# Tray2_ARM.net
KiCad netlist of a schematic drawn in Altium Designer
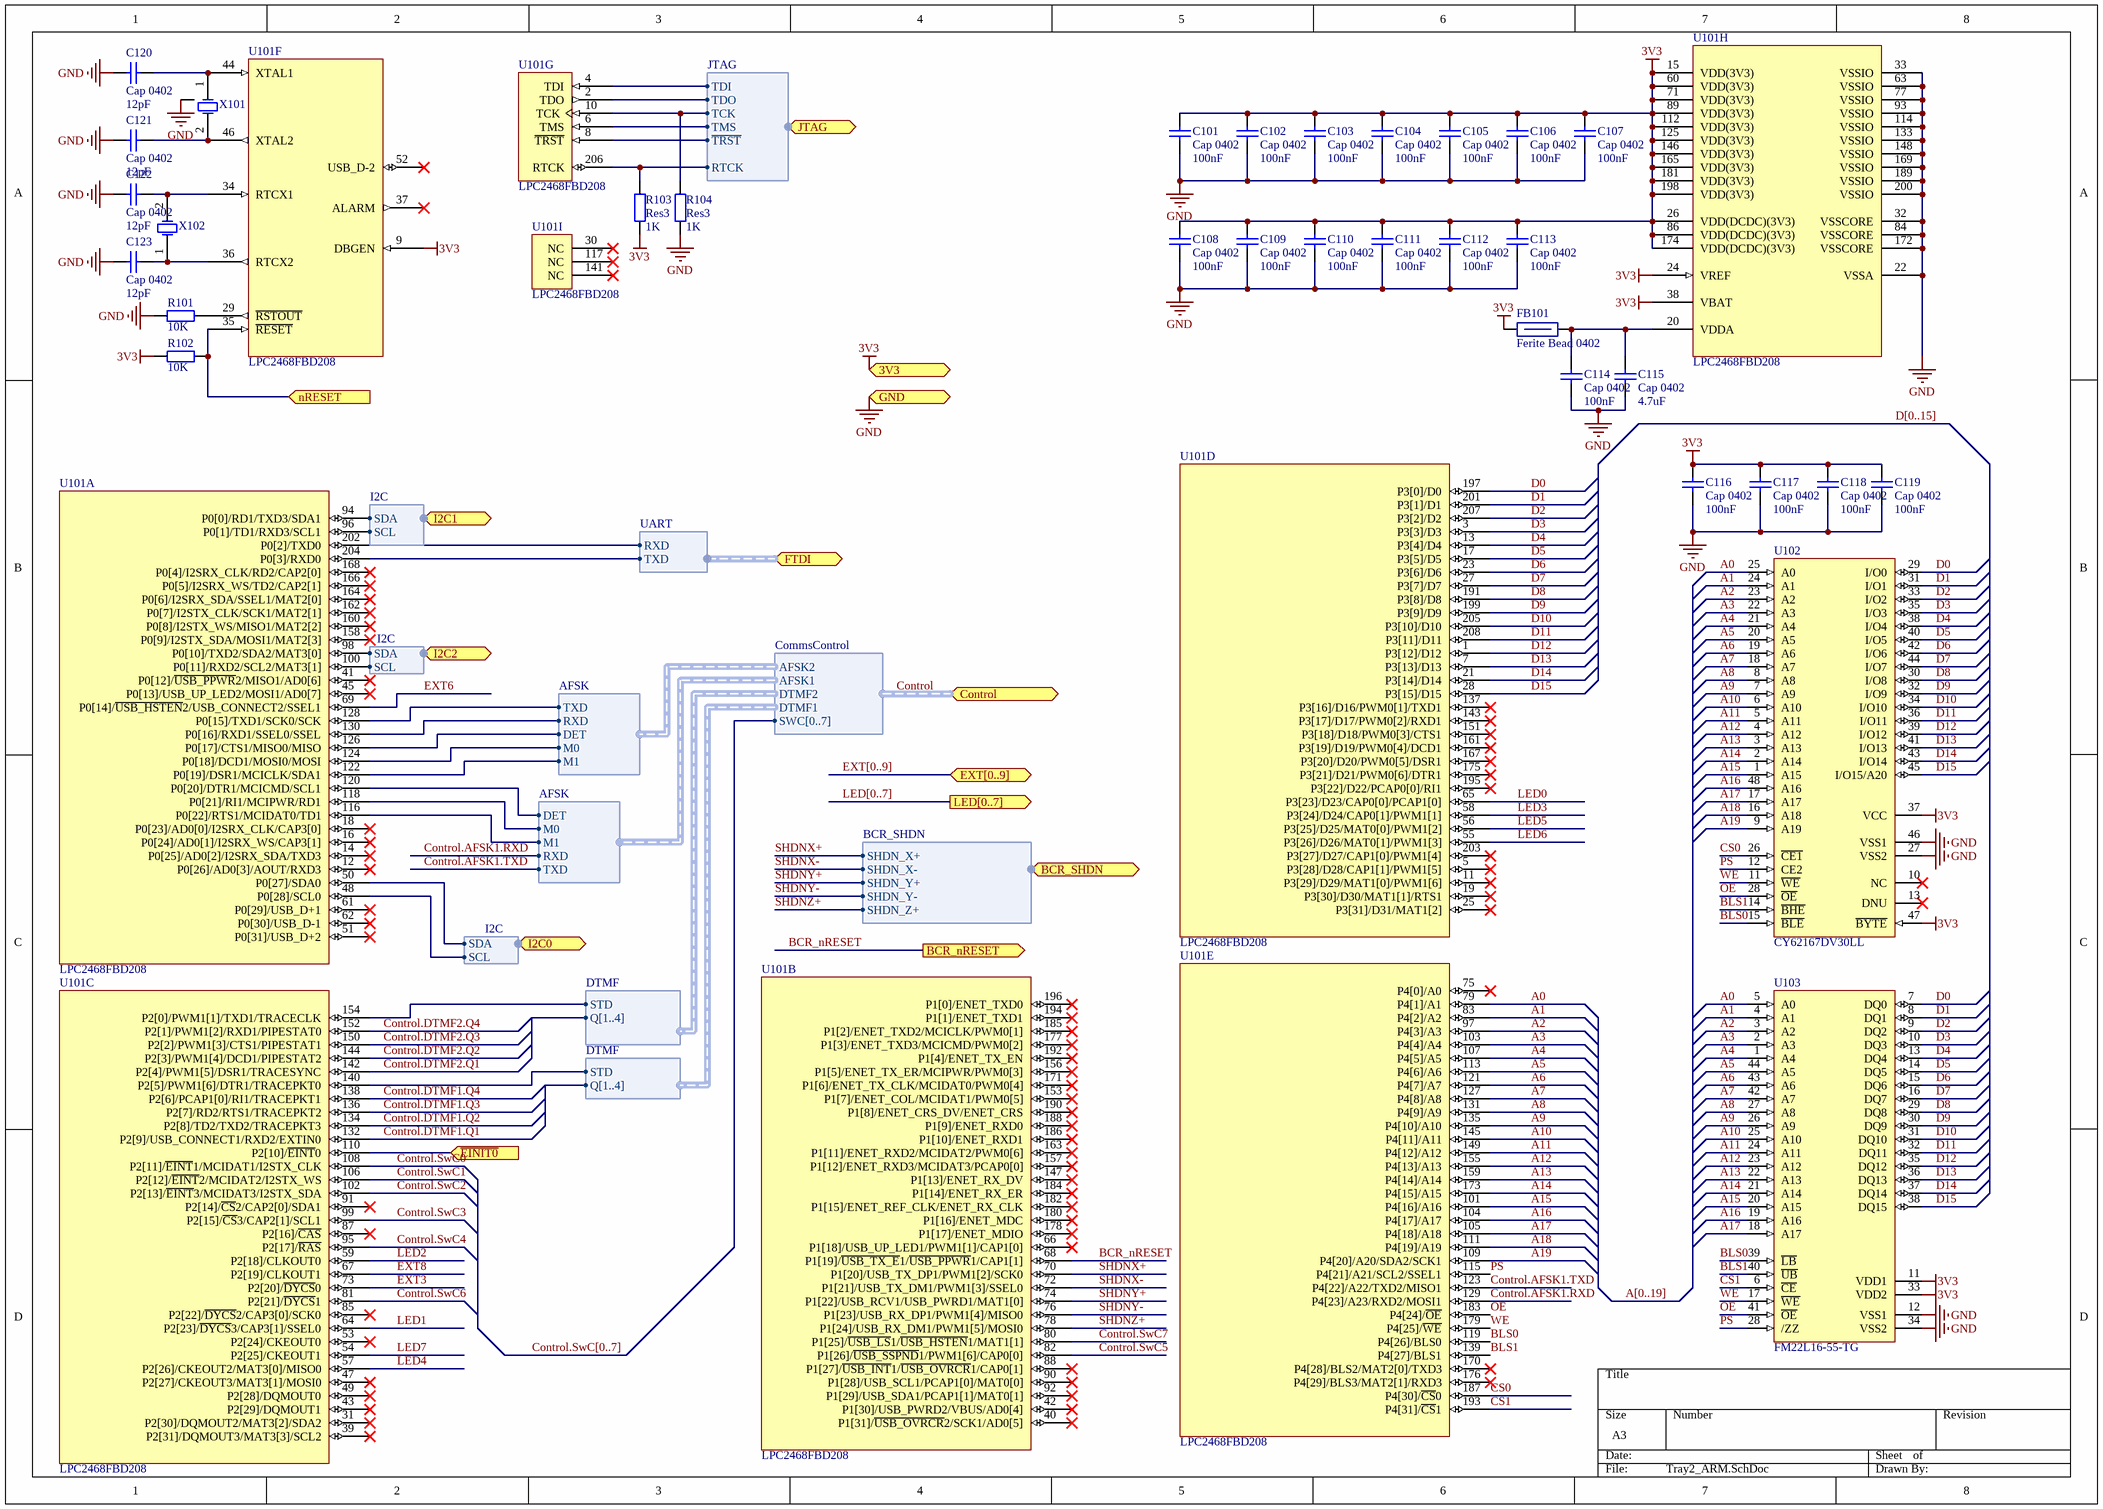
[diagram p0: Tray2_ARM.SchDoc]

(export (version "E")
  (design (tool "Eeschema 10.0.6"))
  (components
    (comp (ref "C101")
      (value "Cap 0402")
      (footprint "CAPC1005X06L")
      (description "Capacitor")
      (fields (field (name "ALTIUM_VALUE") "100nF") (field (name "PUBLISHER") "Altium Limited"))
      (libsource (lib "CSC") (part "Cap 0402"))
    )
    (comp (ref "C102")
      (value "Cap 0402")
      (footprint "CAPC1005X06L")
      (description "Capacitor")
      (fields (field (name "ALTIUM_VALUE") "100nF") (field (name "PUBLISHER") "Altium Limited"))
      (libsource (lib "CSC") (part "Cap 0402"))
    )
    (comp (ref "C103")
      (value "Cap 0402")
      (footprint "CAPC1005X06L")
      (description "Capacitor")
      (fields (field (name "ALTIUM_VALUE") "100nF") (field (name "PUBLISHER") "Altium Limited"))
      (libsource (lib "CSC") (part "Cap 0402"))
    )
    (comp (ref "C104")
      (value "Cap 0402")
      (footprint "CAPC1005X06L")
      (description "Capacitor")
      (fields (field (name "ALTIUM_VALUE") "100nF") (field (name "PUBLISHER") "Altium Limited"))
      (libsource (lib "CSC") (part "Cap 0402"))
    )
    (comp (ref "C105")
      (value "Cap 0402")
      (footprint "CAPC1005X06L")
      (description "Capacitor")
      (fields (field (name "ALTIUM_VALUE") "100nF") (field (name "PUBLISHER") "Altium Limited"))
      (libsource (lib "CSC") (part "Cap 0402"))
    )
    (comp (ref "C106")
      (value "Cap 0402")
      (footprint "CAPC1005X06L")
      (description "Capacitor")
      (fields (field (name "ALTIUM_VALUE") "100nF") (field (name "PUBLISHER") "Altium Limited"))
      (libsource (lib "CSC") (part "Cap 0402"))
    )
    (comp (ref "C107")
      (value "Cap 0402")
      (footprint "CAPC1005X06L")
      (description "Capacitor")
      (fields (field (name "ALTIUM_VALUE") "100nF") (field (name "PUBLISHER") "Altium Limited"))
      (libsource (lib "CSC") (part "Cap 0402"))
    )
    (comp (ref "C108")
      (value "Cap 0402")
      (footprint "CAPC1005X06L")
      (description "Capacitor")
      (fields (field (name "ALTIUM_VALUE") "100nF") (field (name "PUBLISHER") "Altium Limited"))
      (libsource (lib "CSC") (part "Cap 0402"))
    )
    (comp (ref "C109")
      (value "Cap 0402")
      (footprint "CAPC1005X06L")
      (description "Capacitor")
      (fields (field (name "ALTIUM_VALUE") "100nF") (field (name "PUBLISHER") "Altium Limited"))
      (libsource (lib "CSC") (part "Cap 0402"))
    )
    (comp (ref "C110")
      (value "Cap 0402")
      (footprint "CAPC1005X06L")
      (description "Capacitor")
      (fields (field (name "ALTIUM_VALUE") "100nF") (field (name "PUBLISHER") "Altium Limited"))
      (libsource (lib "CSC") (part "Cap 0402"))
    )
    (comp (ref "C111")
      (value "Cap 0402")
      (footprint "CAPC1005X06L")
      (description "Capacitor")
      (fields (field (name "ALTIUM_VALUE") "100nF") (field (name "PUBLISHER") "Altium Limited"))
      (libsource (lib "CSC") (part "Cap 0402"))
    )
    (comp (ref "C112")
      (value "Cap 0402")
      (footprint "CAPC1005X06L")
      (description "Capacitor")
      (fields (field (name "ALTIUM_VALUE") "100nF") (field (name "PUBLISHER") "Altium Limited"))
      (libsource (lib "CSC") (part "Cap 0402"))
    )
    (comp (ref "C113")
      (value "Cap 0402")
      (footprint "CAPC1005X06L")
      (description "Capacitor")
      (fields (field (name "ALTIUM_VALUE") "100nF") (field (name "PUBLISHER") "Altium Limited"))
      (libsource (lib "CSC") (part "Cap 0402"))
    )
    (comp (ref "C114")
      (value "Cap 0402")
      (footprint "CAPC1005X06L")
      (description "Capacitor")
      (fields (field (name "ALTIUM_VALUE") "100nF") (field (name "PUBLISHER") "Altium Limited"))
      (libsource (lib "CSC") (part "Cap 0402"))
    )
    (comp (ref "C115")
      (value "Cap 0402")
      (footprint "CAPC1005X06L")
      (description "Capacitor")
      (fields (field (name "ALTIUM_VALUE") "4.7uF") (field (name "PUBLISHER") "Altium Limited"))
      (libsource (lib "CSC") (part "Cap 0402"))
    )
    (comp (ref "C116")
      (value "Cap 0402")
      (footprint "CAPC1005X06L")
      (description "Capacitor")
      (fields (field (name "ALTIUM_VALUE") "100nF") (field (name "PUBLISHER") "Altium Limited"))
      (libsource (lib "CSC") (part "Cap 0402"))
    )
    (comp (ref "C117")
      (value "Cap 0402")
      (footprint "CAPC1005X06L")
      (description "Capacitor")
      (fields (field (name "ALTIUM_VALUE") "100nF") (field (name "PUBLISHER") "Altium Limited"))
      (libsource (lib "CSC") (part "Cap 0402"))
    )
    (comp (ref "C118")
      (value "Cap 0402")
      (footprint "CAPC1005X06L")
      (description "Capacitor")
      (fields (field (name "ALTIUM_VALUE") "100nF") (field (name "PUBLISHER") "Altium Limited"))
      (libsource (lib "CSC") (part "Cap 0402"))
    )
    (comp (ref "C119")
      (value "Cap 0402")
      (footprint "CAPC1005X06L")
      (description "Capacitor")
      (fields (field (name "ALTIUM_VALUE") "100nF") (field (name "PUBLISHER") "Altium Limited"))
      (libsource (lib "CSC") (part "Cap 0402"))
    )
    (comp (ref "C120")
      (value "Cap 0402")
      (footprint "CAPC1005X06L")
      (description "Capacitor")
      (fields (field (name "ALTIUM_VALUE") "12pF") (field (name "PUBLISHER") "Altium Limited"))
      (libsource (lib "CSC") (part "Cap 0402"))
    )
    (comp (ref "C121")
      (value "Cap 0402")
      (footprint "CAPC1005X06L")
      (description "Capacitor")
      (fields (field (name "ALTIUM_VALUE") "12pF") (field (name "PUBLISHER") "Altium Limited"))
      (libsource (lib "CSC") (part "Cap 0402"))
    )
    (comp (ref "C122")
      (value "Cap 0402")
      (footprint "CAPC1005X06L")
      (description "Capacitor")
      (fields (field (name "ALTIUM_VALUE") "12pF") (field (name "PUBLISHER") "Altium Limited"))
      (libsource (lib "CSC") (part "Cap 0402"))
    )
    (comp (ref "C123")
      (value "Cap 0402")
      (footprint "CAPC1005X06L")
      (description "Capacitor")
      (fields (field (name "ALTIUM_VALUE") "12pF") (field (name "PUBLISHER") "Altium Limited"))
      (libsource (lib "CSC") (part "Cap 0402"))
    )
    (comp (ref "FB101")
      (value "Ferite Bead 0402")
      (footprint "INDC1005X06L")
      (description "Ferite Bead : 0402")
      (fields (field (name "PUBLISHER") "Altium Limited"))
      (libsource (lib "CSC") (part "FB_0402"))
    )
    (comp (ref "R101")
      (value "10K")
      (footprint "RESC1005X06L")
      (description "Resistor")
      (fields (field (name "Comment") "Res3") (field (name "PUBLISHER") "Altium Limited"))
      (libsource (lib "") (part "Res3_1"))
    )
    (comp (ref "R102")
      (value "10K")
      (footprint "RESC1005X06L")
      (description "Resistor")
      (fields (field (name "Comment") "Res3") (field (name "PUBLISHER") "Altium Limited"))
      (libsource (lib "") (part "Res3_1"))
    )
    (comp (ref "R103")
      (value "Res3")
      (footprint "RESC1005X06L")
      (description "Resistor")
      (fields (field (name "ALTIUM_VALUE") "1K") (field (name "PUBLISHER") "Altium Limited"))
      (libsource (lib "CSC") (part "Res3"))
    )
    (comp (ref "R104")
      (value "Res3")
      (footprint "RESC1005X06L")
      (description "Resistor")
      (fields (field (name "ALTIUM_VALUE") "1K") (field (name "PUBLISHER") "Altium Limited"))
      (libsource (lib "CSC") (part "Res3"))
    )
    (comp (ref "U101")
      (value "LPC2468FBD208")
      (footprint "TSQFP50P3000X3000X160-208L")
      (description "ARM7 16/32-Bit Microcontroller, 512KB Flash, 98KB RAM, 208-Lead LQFP")
      (fields (field (name "PUBLISHER") "Altium Limited"))
      (libsource (lib "CSC") (part "LPC2468FBD208"))
    )
    (comp (ref "U102")
      (value "CY62167DV30LL")
      (footprint "TSSOP50P2000X120-48L")
      (description "16-Mbit (1M x 16) Static RAM")
      (fields (field (name "PUBLISHER") "Altium Limited"))
      (libsource (lib "CSC") (part "CY62167DV30LL"))
    )
    (comp (ref "U103")
      (value "FM22L16-55-TG")
      (footprint "TSOP80P1180X120-44L")
      (description "FRAM, 2MB, 3V, 60NS, 44TSOP2")
      (libsource (lib "CSC") (part "FM22L16-55-TG"))
    )
    (comp (ref "X101")
      (value "Crystal Oscilator")
      (footprint "7M")
      (description "Crystal Oscillator")
      (fields (field (name "PUBLISHER") "Altium Limited"))
      (libsource (lib "CSC") (part "C.O. 4pins"))
    )
    (comp (ref "X102")
      (value "Crystal Oscilator")
      (footprint "9H T10")
      (description "Crystal Oscillator")
      (fields (field (name "PUBLISHER") "Altium Limited"))
      (libsource (lib "CSC") (part "C.O. 2pins"))
    )
  )
  (nets
    (net (code "15") (name "/A0") (class "Default")
      (node (ref "U101") (pin "79") (pinfunction "P4[1]/A1_79") (pintype "bidirectional"))
      (node (ref "U102") (pin "25") (pinfunction "A0_25") (pintype "input"))
      (node (ref "U103") (pin "5") (pinfunction "A0_5") (pintype "input"))
    )
    (net (code "16") (name "/A1") (class "Default")
      (node (ref "U101") (pin "83") (pinfunction "P4[2]/A2_83") (pintype "bidirectional"))
      (node (ref "U102") (pin "24") (pinfunction "A1_24") (pintype "input"))
      (node (ref "U103") (pin "4") (pinfunction "A1_4") (pintype "input"))
    )
    (net (code "17") (name "/A2") (class "Default")
      (node (ref "U101") (pin "97") (pinfunction "P4[3]/A3_97") (pintype "bidirectional"))
      (node (ref "U102") (pin "23") (pinfunction "A2_23") (pintype "input"))
      (node (ref "U103") (pin "3") (pinfunction "A2_3") (pintype "input"))
    )
    (net (code "18") (name "/A3") (class "Default")
      (node (ref "U101") (pin "103") (pinfunction "P4[4]/A4_103") (pintype "bidirectional"))
      (node (ref "U102") (pin "22") (pinfunction "A3_22") (pintype "input"))
      (node (ref "U103") (pin "2") (pinfunction "A3_2") (pintype "input"))
    )
    (net (code "19") (name "/A4") (class "Default")
      (node (ref "U101") (pin "107") (pinfunction "P4[5]/A5_107") (pintype "bidirectional"))
      (node (ref "U102") (pin "21") (pinfunction "A4_21") (pintype "input"))
      (node (ref "U103") (pin "1") (pinfunction "A4_1") (pintype "input"))
    )
    (net (code "20") (name "/A5") (class "Default")
      (node (ref "U101") (pin "113") (pinfunction "P4[6]/A6_113") (pintype "bidirectional"))
      (node (ref "U102") (pin "20") (pinfunction "A5_20") (pintype "input"))
      (node (ref "U103") (pin "44") (pinfunction "A5_44") (pintype "input"))
    )
    (net (code "21") (name "/A6") (class "Default")
      (node (ref "U101") (pin "121") (pinfunction "P4[7]/A7_121") (pintype "bidirectional"))
      (node (ref "U102") (pin "19") (pinfunction "A6_19") (pintype "input"))
      (node (ref "U103") (pin "43") (pinfunction "A6_43") (pintype "input"))
    )
    (net (code "22") (name "/A7") (class "Default")
      (node (ref "U101") (pin "127") (pinfunction "P4[8]/A8_127") (pintype "bidirectional"))
      (node (ref "U102") (pin "18") (pinfunction "A7_18") (pintype "input"))
      (node (ref "U103") (pin "42") (pinfunction "A7_42") (pintype "input"))
    )
    (net (code "23") (name "/A8") (class "Default")
      (node (ref "U101") (pin "131") (pinfunction "P4[9]/A9_131") (pintype "bidirectional"))
      (node (ref "U102") (pin "8") (pinfunction "A8_8") (pintype "input"))
      (node (ref "U103") (pin "27") (pinfunction "A8_27") (pintype "input"))
    )
    (net (code "24") (name "/A9") (class "Default")
      (node (ref "U101") (pin "135") (pinfunction "P4[10]/A10_135") (pintype "bidirectional"))
      (node (ref "U102") (pin "7") (pinfunction "A9_7") (pintype "input"))
      (node (ref "U103") (pin "26") (pinfunction "A9_26") (pintype "input"))
    )
    (net (code "25") (name "/A10") (class "Default")
      (node (ref "U101") (pin "145") (pinfunction "P4[11]/A11_145") (pintype "bidirectional"))
      (node (ref "U102") (pin "6") (pinfunction "A10_6") (pintype "input"))
      (node (ref "U103") (pin "25") (pinfunction "A10_25") (pintype "input"))
    )
    (net (code "26") (name "/A11") (class "Default")
      (node (ref "U101") (pin "149") (pinfunction "P4[12]/A12_149") (pintype "bidirectional"))
      (node (ref "U102") (pin "5") (pinfunction "A11_5") (pintype "input"))
      (node (ref "U103") (pin "24") (pinfunction "A11_24") (pintype "input"))
    )
    (net (code "27") (name "/A12") (class "Default")
      (node (ref "U101") (pin "155") (pinfunction "P4[13]/A13_155") (pintype "bidirectional"))
      (node (ref "U102") (pin "4") (pinfunction "A12_4") (pintype "input"))
      (node (ref "U103") (pin "23") (pinfunction "A12_23") (pintype "input"))
    )
    (net (code "28") (name "/A13") (class "Default")
      (node (ref "U101") (pin "159") (pinfunction "P4[14]/A14_159") (pintype "bidirectional"))
      (node (ref "U102") (pin "3") (pinfunction "A13_3") (pintype "input"))
      (node (ref "U103") (pin "22") (pinfunction "A13_22") (pintype "input"))
    )
    (net (code "29") (name "/A14") (class "Default")
      (node (ref "U101") (pin "173") (pinfunction "P4[15]/A15_173") (pintype "bidirectional"))
      (node (ref "U102") (pin "2") (pinfunction "A14_2") (pintype "input"))
      (node (ref "U103") (pin "21") (pinfunction "A14_21") (pintype "input"))
    )
    (net (code "30") (name "/A15") (class "Default")
      (node (ref "U101") (pin "101") (pinfunction "P4[16]/A16_101") (pintype "bidirectional"))
      (node (ref "U102") (pin "1") (pinfunction "A15_1") (pintype "input"))
      (node (ref "U103") (pin "20") (pinfunction "A15_20") (pintype "input"))
    )
    (net (code "31") (name "/A16") (class "Default")
      (node (ref "U101") (pin "104") (pinfunction "P4[17]/A17_104") (pintype "bidirectional"))
      (node (ref "U102") (pin "48") (pinfunction "A16_48") (pintype "input"))
      (node (ref "U103") (pin "19") (pinfunction "A16_19") (pintype "input"))
    )
    (net (code "32") (name "/A17") (class "Default")
      (node (ref "U101") (pin "105") (pinfunction "P4[18]/A18_105") (pintype "bidirectional"))
      (node (ref "U102") (pin "17") (pinfunction "A17_17") (pintype "input"))
      (node (ref "U103") (pin "18") (pinfunction "A17_18") (pintype "input"))
    )
    (net (code "33") (name "/A18") (class "Default")
      (node (ref "U101") (pin "111") (pinfunction "P4[19]/A19_111") (pintype "bidirectional"))
      (node (ref "U102") (pin "16") (pinfunction "A18_16") (pintype "input"))
    )
    (net (code "34") (name "/A19") (class "Default")
      (node (ref "U101") (pin "109") (pinfunction "P4[20]/A20/SDA2/SCK1_109") (pintype "bidirectional"))
      (node (ref "U102") (pin "9") (pinfunction "A19_9") (pintype "input"))
    )
    (net (code "36") (name "/BCR_nRESET") (class "Default")
      (node (ref "U101") (pin "68") (pinfunction "P1[19]/~{USB_TX_E}1/~{USB_PPWR}1/CAP1[1]_68") (pintype "bidirectional"))
    )
    (net (code "37") (name "/BLS0") (class "Default")
      (node (ref "U101") (pin "119") (pinfunction "P4[26]/BLS0_119") (pintype "bidirectional"))
      (node (ref "U102") (pin "15") (pinfunction "~{BLE}_15") (pintype "input"))
      (node (ref "U103") (pin "39") (pinfunction "~{LB}_39") (pintype "input"))
    )
    (net (code "38") (name "/BLS1") (class "Default")
      (node (ref "U101") (pin "139") (pinfunction "P4[27]/BLS1_139") (pintype "bidirectional"))
      (node (ref "U102") (pin "14") (pinfunction "~{BHE}_14") (pintype "input"))
      (node (ref "U103") (pin "40") (pinfunction "~{UB}_40") (pintype "input"))
    )
    (net (code "39") (name "/CS0") (class "Default")
      (node (ref "U101") (pin "187") (pinfunction "P4[30]/~{CS}0_187") (pintype "bidirectional"))
      (node (ref "U102") (pin "26") (pinfunction "~{CE1}_26") (pintype "input"))
    )
    (net (code "40") (name "/CS1") (class "Default")
      (node (ref "U101") (pin "193") (pinfunction "P4[31]/~{CS}1_193") (pintype "bidirectional"))
      (node (ref "U103") (pin "6") (pinfunction "~{CE}_6") (pintype "input"))
    )
    (net (code "41") (name "/Control.AFSK1.RXD") (class "Default")
      (node (ref "U101") (pin "129") (pinfunction "P4[23]/A23/RXD2/MOSI1_129") (pintype "bidirectional"))
    )
    (net (code "42") (name "/Control.AFSK1.TXD") (class "Default")
      (node (ref "U101") (pin "123") (pinfunction "P4[22]/A22/TXD2/MISO1_123") (pintype "bidirectional"))
    )
    (net (code "43") (name "/Control.DTMF1.Q1") (class "Default")
      (node (ref "U101") (pin "132") (pinfunction "P2[9]/USB_CONNECT1/RXD2/EXTIN0_132") (pintype "bidirectional"))
    )
    (net (code "44") (name "/Control.DTMF1.Q2") (class "Default")
      (node (ref "U101") (pin "134") (pinfunction "P2[8]/TD2/TXD2/TRACEPKT3_134") (pintype "bidirectional"))
    )
    (net (code "45") (name "/Control.DTMF1.Q3") (class "Default")
      (node (ref "U101") (pin "136") (pinfunction "P2[7]/RD2/RTS1/TRACEPKT2_136") (pintype "bidirectional"))
    )
    (net (code "46") (name "/Control.DTMF1.Q4") (class "Default")
      (node (ref "U101") (pin "138") (pinfunction "P2[6]/PCAP1[0]/RI1/TRACEPKT1_138") (pintype "bidirectional"))
    )
    (net (code "47") (name "/Control.DTMF2.Q1") (class "Default")
      (node (ref "U101") (pin "142") (pinfunction "P2[4]/PWM1[5]/DSR1/TRACESYNC_142") (pintype "bidirectional"))
    )
    (net (code "48") (name "/Control.DTMF2.Q2") (class "Default")
      (node (ref "U101") (pin "144") (pinfunction "P2[3]/PWM1[4]/DCD1/PIPESTAT2_144") (pintype "bidirectional"))
    )
    (net (code "49") (name "/Control.DTMF2.Q3") (class "Default")
      (node (ref "U101") (pin "150") (pinfunction "P2[2]/PWM1[3]/CTS1/PIPESTAT1_150") (pintype "bidirectional"))
    )
    (net (code "50") (name "/Control.DTMF2.Q4") (class "Default")
      (node (ref "U101") (pin "152") (pinfunction "P2[1]/PWM1[2]/RXD1/PIPESTAT0_152") (pintype "bidirectional"))
    )
    (net (code "51") (name "/Control.SwC0") (class "Default")
      (node (ref "U101") (pin "108") (pinfunction "P2[11]/~{EINT}1/MCIDAT1/I2STX_CLK_108") (pintype "bidirectional"))
    )
    (net (code "52") (name "/Control.SwC1") (class "Default")
      (node (ref "U101") (pin "106") (pinfunction "P2[12]/~{EINT}2/MCIDAT2/I2STX_WS_106") (pintype "bidirectional"))
    )
    (net (code "53") (name "/Control.SwC2") (class "Default")
      (node (ref "U101") (pin "102") (pinfunction "P2[13]/~{EINT}3/MCIDAT3/I2STX_SDA_102") (pintype "bidirectional"))
    )
    (net (code "54") (name "/Control.SwC3") (class "Default")
      (node (ref "U101") (pin "99") (pinfunction "P2[15]/~{CS}3/CAP2[1]/SCL1_99") (pintype "bidirectional"))
    )
    (net (code "55") (name "/Control.SwC4") (class "Default")
      (node (ref "U101") (pin "95") (pinfunction "P2[17]/~{RAS}_95") (pintype "bidirectional"))
    )
    (net (code "56") (name "/Control.SwC5") (class "Default")
      (node (ref "U101") (pin "82") (pinfunction "P1[26]/~{USB_SSPND}1/PWM1[6]/CAP0[0]_82") (pintype "bidirectional"))
    )
    (net (code "57") (name "/Control.SwC6") (class "Default")
      (node (ref "U101") (pin "81") (pinfunction "P2[21]/~{DYCS}1_81") (pintype "bidirectional"))
    )
    (net (code "58") (name "/Control.SwC7") (class "Default")
      (node (ref "U101") (pin "80") (pinfunction "P1[25]/~{USB_LS}1/~{USB_HSTEN}1/MAT1[1]_80") (pintype "bidirectional"))
    )
    (net (code "59") (name "/D0") (class "Default")
      (node (ref "U101") (pin "197") (pinfunction "P3[0]/D0_197") (pintype "bidirectional"))
      (node (ref "U102") (pin "29") (pinfunction "I/O0_29") (pintype "bidirectional"))
      (node (ref "U103") (pin "7") (pinfunction "DQ0_7") (pintype "bidirectional"))
    )
    (net (code "60") (name "/D1") (class "Default")
      (node (ref "U101") (pin "201") (pinfunction "P3[1]/D1_201") (pintype "bidirectional"))
      (node (ref "U102") (pin "31") (pinfunction "I/O1_31") (pintype "bidirectional"))
      (node (ref "U103") (pin "8") (pinfunction "DQ1_8") (pintype "bidirectional"))
    )
    (net (code "61") (name "/D2") (class "Default")
      (node (ref "U101") (pin "207") (pinfunction "P3[2]/D2_207") (pintype "bidirectional"))
      (node (ref "U102") (pin "33") (pinfunction "I/O2_33") (pintype "bidirectional"))
      (node (ref "U103") (pin "9") (pinfunction "DQ2_9") (pintype "bidirectional"))
    )
    (net (code "62") (name "/D3") (class "Default")
      (node (ref "U101") (pin "3") (pinfunction "P3[3]/D3_3") (pintype "bidirectional"))
      (node (ref "U102") (pin "35") (pinfunction "I/O3_35") (pintype "bidirectional"))
      (node (ref "U103") (pin "10") (pinfunction "DQ3_10") (pintype "bidirectional"))
    )
    (net (code "63") (name "/D4") (class "Default")
      (node (ref "U101") (pin "13") (pinfunction "P3[4]/D4_13") (pintype "bidirectional"))
      (node (ref "U102") (pin "38") (pinfunction "I/O4_38") (pintype "bidirectional"))
      (node (ref "U103") (pin "13") (pinfunction "DQ4_13") (pintype "bidirectional"))
    )
    (net (code "64") (name "/D5") (class "Default")
      (node (ref "U101") (pin "17") (pinfunction "P3[5]/D5_17") (pintype "bidirectional"))
      (node (ref "U102") (pin "40") (pinfunction "I/O5_40") (pintype "bidirectional"))
      (node (ref "U103") (pin "14") (pinfunction "DQ5_14") (pintype "bidirectional"))
    )
    (net (code "65") (name "/D6") (class "Default")
      (node (ref "U101") (pin "23") (pinfunction "P3[6]/D6_23") (pintype "bidirectional"))
      (node (ref "U102") (pin "42") (pinfunction "I/O6_42") (pintype "bidirectional"))
      (node (ref "U103") (pin "15") (pinfunction "DQ6_15") (pintype "bidirectional"))
    )
    (net (code "66") (name "/D7") (class "Default")
      (node (ref "U101") (pin "27") (pinfunction "P3[7]/D7_27") (pintype "bidirectional"))
      (node (ref "U102") (pin "44") (pinfunction "I/O7_44") (pintype "bidirectional"))
      (node (ref "U103") (pin "16") (pinfunction "DQ7_16") (pintype "bidirectional"))
    )
    (net (code "67") (name "/D8") (class "Default")
      (node (ref "U101") (pin "191") (pinfunction "P3[8]/D8_191") (pintype "bidirectional"))
      (node (ref "U102") (pin "30") (pinfunction "I/O8_30") (pintype "bidirectional"))
      (node (ref "U103") (pin "29") (pinfunction "DQ8_29") (pintype "bidirectional"))
    )
    (net (code "68") (name "/D9") (class "Default")
      (node (ref "U101") (pin "199") (pinfunction "P3[9]/D9_199") (pintype "bidirectional"))
      (node (ref "U102") (pin "32") (pinfunction "I/O9_32") (pintype "bidirectional"))
      (node (ref "U103") (pin "30") (pinfunction "DQ9_30") (pintype "bidirectional"))
    )
    (net (code "69") (name "/D10") (class "Default")
      (node (ref "U101") (pin "205") (pinfunction "P3[10]/D10_205") (pintype "bidirectional"))
      (node (ref "U102") (pin "34") (pinfunction "I/O10_34") (pintype "bidirectional"))
      (node (ref "U103") (pin "31") (pinfunction "DQ10_31") (pintype "bidirectional"))
    )
    (net (code "70") (name "/D11") (class "Default")
      (node (ref "U101") (pin "208") (pinfunction "P3[11]/D11_208") (pintype "bidirectional"))
      (node (ref "U102") (pin "36") (pinfunction "I/O11_36") (pintype "bidirectional"))
      (node (ref "U103") (pin "32") (pinfunction "DQ11_32") (pintype "bidirectional"))
    )
    (net (code "71") (name "/D12") (class "Default")
      (node (ref "U101") (pin "1") (pinfunction "P3[12]/D12_1") (pintype "bidirectional"))
      (node (ref "U102") (pin "39") (pinfunction "I/O12_39") (pintype "bidirectional"))
      (node (ref "U103") (pin "35") (pinfunction "DQ12_35") (pintype "bidirectional"))
    )
    (net (code "72") (name "/D13") (class "Default")
      (node (ref "U101") (pin "7") (pinfunction "P3[13]/D13_7") (pintype "bidirectional"))
      (node (ref "U102") (pin "41") (pinfunction "I/O13_41") (pintype "bidirectional"))
      (node (ref "U103") (pin "36") (pinfunction "DQ13_36") (pintype "bidirectional"))
    )
    (net (code "73") (name "/D14") (class "Default")
      (node (ref "U101") (pin "21") (pinfunction "P3[14]/D14_21") (pintype "bidirectional"))
      (node (ref "U102") (pin "43") (pinfunction "I/O14_43") (pintype "bidirectional"))
      (node (ref "U103") (pin "37") (pinfunction "DQ14_37") (pintype "bidirectional"))
    )
    (net (code "74") (name "/D15") (class "Default")
      (node (ref "U101") (pin "28") (pinfunction "P3[15]/D15_28") (pintype "bidirectional"))
      (node (ref "U102") (pin "45") (pinfunction "I/O15/A20_45") (pintype "bidirectional"))
      (node (ref "U103") (pin "38") (pinfunction "DQ15_38") (pintype "bidirectional"))
    )
    (net (code "77") (name "/EXT3") (class "Default")
      (node (ref "U101") (pin "73") (pinfunction "P2[20]/~{DYCS}0_73") (pintype "bidirectional"))
    )
    (net (code "78") (name "/EXT6") (class "Default")
      (node (ref "U101") (pin "69") (pinfunction "P0[14]/~{USB_HSTEN}2/USB_CONNECT2/SSEL1_69") (pintype "bidirectional"))
    )
    (net (code "79") (name "/EXT8") (class "Default")
      (node (ref "U101") (pin "67") (pinfunction "P2[19]/CLKOUT1_67") (pintype "bidirectional"))
    )
    (net (code "81") (name "/LED0") (class "Default")
      (node (ref "U101") (pin "65") (pinfunction "P3[23]/D23/CAP0[0]/PCAP1[0]_65") (pintype "bidirectional"))
    )
    (net (code "82") (name "/LED1") (class "Default")
      (node (ref "U101") (pin "64") (pinfunction "P2[23]/~{DYCS}3/CAP3[1]/SSEL0_64") (pintype "bidirectional"))
    )
    (net (code "83") (name "/LED2") (class "Default")
      (node (ref "U101") (pin "59") (pinfunction "P2[18]/CLKOUT0_59") (pintype "bidirectional"))
    )
    (net (code "84") (name "/LED3") (class "Default")
      (node (ref "U101") (pin "58") (pinfunction "P3[24]/D24/CAP0[1]/PWM1[1]_58") (pintype "bidirectional"))
    )
    (net (code "85") (name "/LED4") (class "Default")
      (node (ref "U101") (pin "57") (pinfunction "P2[26]/CKEOUT2/MAT3[0]/MISO0_57") (pintype "bidirectional"))
    )
    (net (code "86") (name "/LED5") (class "Default")
      (node (ref "U101") (pin "56") (pinfunction "P3[25]/D25/MAT0[0]/PWM1[2]_56") (pintype "bidirectional"))
    )
    (net (code "87") (name "/LED6") (class "Default")
      (node (ref "U101") (pin "55") (pinfunction "P3[26]/D26/MAT0[1]/PWM1[3]_55") (pintype "bidirectional"))
    )
    (net (code "88") (name "/LED7") (class "Default")
      (node (ref "U101") (pin "54") (pinfunction "P2[25]/CKEOUT1_54") (pintype "bidirectional"))
    )
    (net (code "90") (name "/OE") (class "Default")
      (node (ref "U101") (pin "183") (pinfunction "P4[24]/~{OE}_183") (pintype "bidirectional"))
      (node (ref "U102") (pin "28") (pinfunction "~{OE}_28") (pintype "input"))
      (node (ref "U103") (pin "41") (pinfunction "~{OE}_41") (pintype "input"))
    )
    (net (code "91") (name "/PS") (class "Default")
      (node (ref "U101") (pin "115") (pinfunction "P4[21]/A21/SCL2/SSEL1_115") (pintype "bidirectional"))
      (node (ref "U102") (pin "12") (pinfunction "CE2_12") (pintype "input"))
      (node (ref "U103") (pin "28") (pinfunction "/ZZ_28") (pintype "input"))
    )
    (net (code "92") (name "/RTCK") (class "Default")
      (node (ref "R103") (pin "1") (pinfunction "1_1") (pintype "passive"))
      (node (ref "U101") (pin "206") (pinfunction "RTCK_206") (pintype "bidirectional"))
    )
    (net (code "93") (name "/SHDNX+") (class "Default")
      (node (ref "U101") (pin "70") (pinfunction "P1[20]/USB_TX_DP1/PWM1[2]/SCK0_70") (pintype "bidirectional"))
    )
    (net (code "94") (name "/SHDNX-") (class "Default")
      (node (ref "U101") (pin "72") (pinfunction "P1[21]/USB_TX_DM1/PWM1[3]/SSEL0_72") (pintype "bidirectional"))
    )
    (net (code "95") (name "/SHDNY+") (class "Default")
      (node (ref "U101") (pin "74") (pinfunction "P1[22]/USB_RCV1/USB_PWRD1/MAT1[0]_74") (pintype "bidirectional"))
    )
    (net (code "96") (name "/SHDNY-") (class "Default")
      (node (ref "U101") (pin "76") (pinfunction "P1[23]/USB_RX_DP1/PWM1[4]/MISO0_76") (pintype "bidirectional"))
    )
    (net (code "97") (name "/SHDNZ+") (class "Default")
      (node (ref "U101") (pin "78") (pinfunction "P1[24]/USB_RX_DM1/PWM1[5]/MOSI0_78") (pintype "bidirectional"))
    )
    (net (code "98") (name "/TCK") (class "Default")
      (node (ref "R104") (pin "1") (pinfunction "1_1") (pintype "passive"))
      (node (ref "U101") (pin "10") (pinfunction "TCK_10") (pintype "input"))
    )
    (net (code "99") (name "/TDI") (class "Default")
      (node (ref "U101") (pin "4") (pinfunction "TDI_4") (pintype "input"))
    )
    (net (code "100") (name "/TDO") (class "Default")
      (node (ref "U101") (pin "2") (pinfunction "TDO_2") (pintype "output"))
    )
    (net (code "101") (name "/TMS") (class "Default")
      (node (ref "U101") (pin "6") (pinfunction "TMS_6") (pintype "input"))
    )
    (net (code "102") (name "/WE") (class "Default")
      (node (ref "U101") (pin "179") (pinfunction "P4[25]/~{WE}_179") (pintype "bidirectional"))
      (node (ref "U102") (pin "11") (pinfunction "~{WE}_11") (pintype "input"))
      (node (ref "U103") (pin "17") (pinfunction "~{WE}_17") (pintype "input"))
    )
    (net (code "103") (name "/nRESET") (class "Default")
      (node (ref "R102") (pin "1") (pinfunction "1_1") (pintype "passive"))
      (node (ref "U101") (pin "35") (pinfunction "~{RESET}_35") (pintype "input"))
    )
    (net (code "111") (name "/~{EINIT0}") (class "Default")
      (node (ref "U101") (pin "110") (pinfunction "P2[10]/~{EINT}0_110") (pintype "bidirectional"))
    )
    (net (code "112") (name "/~{TRST}") (class "Default")
      (node (ref "U101") (pin "8") (pinfunction "~{TRST}_8") (pintype "input"))
    )
    (net (code "113") (name "3V3") (class "Default")
      (node (ref "C101") (pin "2") (pinfunction "2_2") (pintype "passive"))
      (node (ref "C102") (pin "2") (pinfunction "2_2") (pintype "passive"))
      (node (ref "C103") (pin "2") (pinfunction "2_2") (pintype "passive"))
      (node (ref "C104") (pin "2") (pinfunction "2_2") (pintype "passive"))
      (node (ref "C105") (pin "2") (pinfunction "2_2") (pintype "passive"))
      (node (ref "C106") (pin "2") (pinfunction "2_2") (pintype "passive"))
      (node (ref "C107") (pin "2") (pinfunction "2_2") (pintype "passive"))
      (node (ref "C108") (pin "2") (pinfunction "2_2") (pintype "passive"))
      (node (ref "C109") (pin "2") (pinfunction "2_2") (pintype "passive"))
      (node (ref "C110") (pin "2") (pinfunction "2_2") (pintype "passive"))
      (node (ref "C111") (pin "2") (pinfunction "2_2") (pintype "passive"))
      (node (ref "C112") (pin "2") (pinfunction "2_2") (pintype "passive"))
      (node (ref "C113") (pin "2") (pinfunction "2_2") (pintype "passive"))
      (node (ref "C116") (pin "2") (pinfunction "2_2") (pintype "passive"))
      (node (ref "C117") (pin "2") (pinfunction "2_2") (pintype "passive"))
      (node (ref "C118") (pin "2") (pinfunction "2_2") (pintype "passive"))
      (node (ref "C119") (pin "2") (pinfunction "2_2") (pintype "passive"))
      (node (ref "FB101") (pin "1") (pinfunction "1_1") (pintype "passive"))
      (node (ref "R102") (pin "2") (pinfunction "2_2") (pintype "passive"))
      (node (ref "R103") (pin "2") (pinfunction "2_2") (pintype "passive"))
      (node (ref "U101") (pin "112") (pinfunction "VDD(3V3)_112") (pintype "power_in"))
      (node (ref "U101") (pin "125") (pinfunction "VDD(3V3)_125") (pintype "power_in"))
      (node (ref "U101") (pin "146") (pinfunction "VDD(3V3)_146") (pintype "power_in"))
      (node (ref "U101") (pin "15") (pinfunction "VDD(3V3)_15") (pintype "power_in"))
      (node (ref "U101") (pin "165") (pinfunction "VDD(3V3)_165") (pintype "power_in"))
      (node (ref "U101") (pin "174") (pinfunction "VDD(DCDC)(3V3)_174") (pintype "power_in"))
      (node (ref "U101") (pin "181") (pinfunction "VDD(3V3)_181") (pintype "power_in"))
      (node (ref "U101") (pin "198") (pinfunction "VDD(3V3)_198") (pintype "power_in"))
      (node (ref "U101") (pin "24") (pinfunction "VREF_24") (pintype "input"))
      (node (ref "U101") (pin "26") (pinfunction "VDD(DCDC)(3V3)_26") (pintype "power_in"))
      (node (ref "U101") (pin "38") (pinfunction "VBAT_38") (pintype "power_in"))
      (node (ref "U101") (pin "60") (pinfunction "VDD(3V3)_60") (pintype "power_in"))
      (node (ref "U101") (pin "71") (pinfunction "VDD(3V3)_71") (pintype "power_in"))
      (node (ref "U101") (pin "86") (pinfunction "VDD(DCDC)(3V3)_86") (pintype "power_in"))
      (node (ref "U101") (pin "89") (pinfunction "VDD(3V3)_89") (pintype "power_in"))
      (node (ref "U101") (pin "9") (pinfunction "DBGEN_9") (pintype "input"))
      (node (ref "U102") (pin "37") (pinfunction "VCC_37") (pintype "power_in"))
      (node (ref "U102") (pin "47") (pinfunction "~{BYTE}_47") (pintype "input"))
      (node (ref "U103") (pin "11") (pinfunction "VDD1_11") (pintype "power_in"))
      (node (ref "U103") (pin "33") (pinfunction "VDD2_33") (pintype "power_in"))
    )
    (net (code "114") (name "GND") (class "Default")
      (node (ref "C101") (pin "1") (pinfunction "1_1") (pintype "passive"))
      (node (ref "C102") (pin "1") (pinfunction "1_1") (pintype "passive"))
      (node (ref "C103") (pin "1") (pinfunction "1_1") (pintype "passive"))
      (node (ref "C104") (pin "1") (pinfunction "1_1") (pintype "passive"))
      (node (ref "C105") (pin "1") (pinfunction "1_1") (pintype "passive"))
      (node (ref "C106") (pin "1") (pinfunction "1_1") (pintype "passive"))
      (node (ref "C107") (pin "1") (pinfunction "1_1") (pintype "passive"))
      (node (ref "C108") (pin "1") (pinfunction "1_1") (pintype "passive"))
      (node (ref "C109") (pin "1") (pinfunction "1_1") (pintype "passive"))
      (node (ref "C110") (pin "1") (pinfunction "1_1") (pintype "passive"))
      (node (ref "C111") (pin "1") (pinfunction "1_1") (pintype "passive"))
      (node (ref "C112") (pin "1") (pinfunction "1_1") (pintype "passive"))
      (node (ref "C113") (pin "1") (pinfunction "1_1") (pintype "passive"))
      (node (ref "C114") (pin "1") (pinfunction "1_1") (pintype "passive"))
      (node (ref "C115") (pin "1") (pinfunction "1_1") (pintype "passive"))
      (node (ref "C116") (pin "1") (pinfunction "1_1") (pintype "passive"))
      (node (ref "C117") (pin "1") (pinfunction "1_1") (pintype "passive"))
      (node (ref "C118") (pin "1") (pinfunction "1_1") (pintype "passive"))
      (node (ref "C119") (pin "1") (pinfunction "1_1") (pintype "passive"))
      (node (ref "C120") (pin "2") (pinfunction "2_2") (pintype "passive"))
      (node (ref "C121") (pin "1") (pinfunction "1_1") (pintype "passive"))
      (node (ref "C122") (pin "2") (pinfunction "2_2") (pintype "passive"))
      (node (ref "C123") (pin "1") (pinfunction "1_1") (pintype "passive"))
      (node (ref "R101") (pin "2") (pinfunction "2_2") (pintype "passive"))
      (node (ref "R104") (pin "2") (pinfunction "2_2") (pintype "passive"))
      (node (ref "U101") (pin "114") (pinfunction "VSSIO_114") (pintype "power_in"))
      (node (ref "U101") (pin "133") (pinfunction "VSSIO_133") (pintype "power_in"))
      (node (ref "U101") (pin "148") (pinfunction "VSSIO_148") (pintype "power_in"))
      (node (ref "U101") (pin "169") (pinfunction "VSSIO_169") (pintype "power_in"))
      (node (ref "U101") (pin "172") (pinfunction "VSSCORE_172") (pintype "power_in"))
      (node (ref "U101") (pin "189") (pinfunction "VSSIO_189") (pintype "power_in"))
      (node (ref "U101") (pin "200") (pinfunction "VSSIO_200") (pintype "power_in"))
      (node (ref "U101") (pin "22") (pinfunction "VSSA_22") (pintype "power_in"))
      (node (ref "U101") (pin "32") (pinfunction "VSSCORE_32") (pintype "power_in"))
      (node (ref "U101") (pin "33") (pinfunction "VSSIO_33") (pintype "power_in"))
      (node (ref "U101") (pin "63") (pinfunction "VSSIO_63") (pintype "power_in"))
      (node (ref "U101") (pin "77") (pinfunction "VSSIO_77") (pintype "power_in"))
      (node (ref "U101") (pin "84") (pinfunction "VSSCORE_84") (pintype "power_in"))
      (node (ref "U101") (pin "93") (pinfunction "VSSIO_93") (pintype "power_in"))
      (node (ref "U102") (pin "27") (pinfunction "VSS2_27") (pintype "power_in"))
      (node (ref "U102") (pin "46") (pinfunction "VSS1_46") (pintype "power_in"))
      (node (ref "U103") (pin "12") (pinfunction "VSS1_12") (pintype "power_in"))
      (node (ref "U103") (pin "34") (pinfunction "VSS2_34") (pintype "power_in"))
      (node (ref "X101") (pin "3") (pinfunction "3_3") (pintype "passive"))
    )
    (net (code "115") (name "Net-(U101F-RTCX1)") (class "Default")
      (node (ref "C122") (pin "1") (pinfunction "1_1") (pintype "passive"))
      (node (ref "U101") (pin "34") (pinfunction "RTCX1_34") (pintype "input"))
      (node (ref "X102") (pin "2") (pinfunction "OSC2_2") (pintype "passive"))
    )
    (net (code "116") (name "Net-(U101F-RTCX2)") (class "Default")
      (node (ref "C123") (pin "2") (pinfunction "2_2") (pintype "passive"))
      (node (ref "U101") (pin "36") (pinfunction "RTCX2_36") (pintype "output"))
      (node (ref "X102") (pin "1") (pinfunction "OSC1_1") (pintype "passive"))
    )
    (net (code "117") (name "Net-(U101F-XTAL1)") (class "Default")
      (node (ref "C120") (pin "1") (pinfunction "1_1") (pintype "passive"))
      (node (ref "U101") (pin "44") (pinfunction "XTAL1_44") (pintype "input"))
      (node (ref "X101") (pin "1") (pinfunction "OSC1_1") (pintype "passive"))
    )
    (net (code "118") (name "Net-(U101F-XTAL2)") (class "Default")
      (node (ref "C121") (pin "2") (pinfunction "2_2") (pintype "passive"))
      (node (ref "U101") (pin "46") (pinfunction "XTAL2_46") (pintype "output"))
      (node (ref "X101") (pin "2") (pinfunction "OSC2_2") (pintype "passive"))
    )
    (net (code "119") (name "Net-(U101F-~{RSTOUT})") (class "Default")
      (node (ref "R101") (pin "1") (pinfunction "1_1") (pintype "passive"))
      (node (ref "U101") (pin "29") (pinfunction "~{RSTOUT}_29") (pintype "output"))
    )
    (net (code "120") (name "Net-(U101H-VDDA)") (class "Default")
      (node (ref "C114") (pin "2") (pinfunction "2_2") (pintype "passive"))
      (node (ref "C115") (pin "2") (pinfunction "2_2") (pintype "passive"))
      (node (ref "FB101") (pin "2") (pinfunction "2_2") (pintype "passive"))
      (node (ref "U101") (pin "20") (pinfunction "VDDA_20") (pintype "power_in"))
    )
    (net (code "121") (name "unconnected-(U101A-P0[0]{slash}RD1{slash}TXD3{slash}SDA1-Pad94)") (class "Default")
      (node (ref "U101") (pin "94") (pinfunction "P0[0]/RD1/TXD3/SDA1_94") (pintype "bidirectional"))
    )
    (net (code "122") (name "unconnected-(U101A-P0[1]{slash}TD1{slash}RXD3{slash}SCL1-Pad96)") (class "Default")
      (node (ref "U101") (pin "96") (pinfunction "P0[1]/TD1/RXD3/SCL1_96") (pintype "bidirectional"))
    )
    (net (code "123") (name "unconnected-(U101A-P0[2]{slash}TXD0-Pad202)") (class "Default")
      (node (ref "U101") (pin "202") (pinfunction "P0[2]/TXD0_202") (pintype "bidirectional"))
    )
    (net (code "124") (name "unconnected-(U101A-P0[3]{slash}RXD0-Pad204)") (class "Default")
      (node (ref "U101") (pin "204") (pinfunction "P0[3]/RXD0_204") (pintype "bidirectional"))
    )
    (net (code "125") (name "unconnected-(U101A-P0[4]{slash}I2SRX_CLK{slash}RD2{slash}CAP2[0]-Pad168)") (class "Default")
      (node (ref "U101") (pin "168") (pinfunction "P0[4]/I2SRX_CLK/RD2/CAP2[0]_168") (pintype "bidirectional+no_connect"))
    )
    (net (code "126") (name "unconnected-(U101A-P0[5]{slash}I2SRX_WS{slash}TD2{slash}CAP2[1]-Pad166)") (class "Default")
      (node (ref "U101") (pin "166") (pinfunction "P0[5]/I2SRX_WS/TD2/CAP2[1]_166") (pintype "bidirectional+no_connect"))
    )
    (net (code "127") (name "unconnected-(U101A-P0[6]{slash}I2SRX_SDA{slash}SSEL1{slash}MAT2[0]-Pad164)") (class "Default")
      (node (ref "U101") (pin "164") (pinfunction "P0[6]/I2SRX_SDA/SSEL1/MAT2[0]_164") (pintype "bidirectional+no_connect"))
    )
    (net (code "128") (name "unconnected-(U101A-P0[7]{slash}I2STX_CLK{slash}SCK1{slash}MAT2[1]-Pad162)") (class "Default")
      (node (ref "U101") (pin "162") (pinfunction "P0[7]/I2STX_CLK/SCK1/MAT2[1]_162") (pintype "bidirectional+no_connect"))
    )
    (net (code "129") (name "unconnected-(U101A-P0[8]{slash}I2STX_WS{slash}MISO1{slash}MAT2[2]-Pad160)") (class "Default")
      (node (ref "U101") (pin "160") (pinfunction "P0[8]/I2STX_WS/MISO1/MAT2[2]_160") (pintype "bidirectional+no_connect"))
    )
    (net (code "130") (name "unconnected-(U101A-P0[9]{slash}I2STX_SDA{slash}MOSI1{slash}MAT2[3]-Pad158)") (class "Default")
      (node (ref "U101") (pin "158") (pinfunction "P0[9]/I2STX_SDA/MOSI1/MAT2[3]_158") (pintype "bidirectional+no_connect"))
    )
    (net (code "131") (name "unconnected-(U101A-P0[10]{slash}TXD2{slash}SDA2{slash}MAT3[0]-Pad98)") (class "Default")
      (node (ref "U101") (pin "98") (pinfunction "P0[10]/TXD2/SDA2/MAT3[0]_98") (pintype "bidirectional"))
    )
    (net (code "132") (name "unconnected-(U101A-P0[11]{slash}RXD2{slash}SCL2{slash}MAT3[1]-Pad100)") (class "Default")
      (node (ref "U101") (pin "100") (pinfunction "P0[11]/RXD2/SCL2/MAT3[1]_100") (pintype "bidirectional"))
    )
    (net (code "133") (name "unconnected-(U101A-P0[12]{slash}~{USB_PPWR}2{slash}MISO1{slash}AD0[6]-Pad41)") (class "Default")
      (node (ref "U101") (pin "41") (pinfunction "P0[12]/~{USB_PPWR}2/MISO1/AD0[6]_41") (pintype "bidirectional+no_connect"))
    )
    (net (code "134") (name "unconnected-(U101A-P0[13]{slash}USB_UP_LED2{slash}MOSI1{slash}AD0[7]-Pad45)") (class "Default")
      (node (ref "U101") (pin "45") (pinfunction "P0[13]/USB_UP_LED2/MOSI1/AD0[7]_45") (pintype "bidirectional+no_connect"))
    )
    (net (code "135") (name "unconnected-(U101A-P0[15]{slash}TXD1{slash}SCK0{slash}SCK-Pad128)") (class "Default")
      (node (ref "U101") (pin "128") (pinfunction "P0[15]/TXD1/SCK0/SCK_128") (pintype "bidirectional"))
    )
    (net (code "136") (name "unconnected-(U101A-P0[16]{slash}RXD1{slash}SSEL0{slash}SSEL-Pad130)") (class "Default")
      (node (ref "U101") (pin "130") (pinfunction "P0[16]/RXD1/SSEL0/SSEL_130") (pintype "bidirectional"))
    )
    (net (code "137") (name "unconnected-(U101A-P0[17]{slash}CTS1{slash}MISO0{slash}MISO-Pad126)") (class "Default")
      (node (ref "U101") (pin "126") (pinfunction "P0[17]/CTS1/MISO0/MISO_126") (pintype "bidirectional"))
    )
    (net (code "138") (name "unconnected-(U101A-P0[18]{slash}DCD1{slash}MOSI0{slash}MOSI-Pad124)") (class "Default")
      (node (ref "U101") (pin "124") (pinfunction "P0[18]/DCD1/MOSI0/MOSI_124") (pintype "bidirectional"))
    )
    (net (code "139") (name "unconnected-(U101A-P0[19]{slash}DSR1{slash}MCICLK{slash}SDA1-Pad122)") (class "Default")
      (node (ref "U101") (pin "122") (pinfunction "P0[19]/DSR1/MCICLK/SDA1_122") (pintype "bidirectional"))
    )
    (net (code "140") (name "unconnected-(U101A-P0[20]{slash}DTR1{slash}MCICMD{slash}SCL1-Pad120)") (class "Default")
      (node (ref "U101") (pin "120") (pinfunction "P0[20]/DTR1/MCICMD/SCL1_120") (pintype "bidirectional"))
    )
    (net (code "141") (name "unconnected-(U101A-P0[21]{slash}RI1{slash}MCIPWR{slash}RD1-Pad118)") (class "Default")
      (node (ref "U101") (pin "118") (pinfunction "P0[21]/RI1/MCIPWR/RD1_118") (pintype "bidirectional"))
    )
    (net (code "142") (name "unconnected-(U101A-P0[22]{slash}RTS1{slash}MCIDAT0{slash}TD1-Pad116)") (class "Default")
      (node (ref "U101") (pin "116") (pinfunction "P0[22]/RTS1/MCIDAT0/TD1_116") (pintype "bidirectional"))
    )
    (net (code "143") (name "unconnected-(U101A-P0[23]{slash}AD0[0]{slash}I2SRX_CLK{slash}CAP3[0]-Pad18)") (class "Default")
      (node (ref "U101") (pin "18") (pinfunction "P0[23]/AD0[0]/I2SRX_CLK/CAP3[0]_18") (pintype "bidirectional+no_connect"))
    )
    (net (code "144") (name "unconnected-(U101A-P0[24]{slash}AD0[1]{slash}I2SRX_WS{slash}CAP3[1]-Pad16)") (class "Default")
      (node (ref "U101") (pin "16") (pinfunction "P0[24]/AD0[1]/I2SRX_WS/CAP3[1]_16") (pintype "bidirectional+no_connect"))
    )
    (net (code "145") (name "unconnected-(U101A-P0[25]{slash}AD0[2]{slash}I2SRX_SDA{slash}TXD3-Pad14)") (class "Default")
      (node (ref "U101") (pin "14") (pinfunction "P0[25]/AD0[2]/I2SRX_SDA/TXD3_14") (pintype "bidirectional+no_connect"))
    )
    (net (code "146") (name "unconnected-(U101A-P0[26]{slash}AD0[3]{slash}AOUT{slash}RXD3-Pad12)") (class "Default")
      (node (ref "U101") (pin "12") (pinfunction "P0[26]/AD0[3]/AOUT/RXD3_12") (pintype "bidirectional+no_connect"))
    )
    (net (code "147") (name "unconnected-(U101A-P0[27]{slash}SDA0-Pad50)") (class "Default")
      (node (ref "U101") (pin "50") (pinfunction "P0[27]/SDA0_50") (pintype "bidirectional"))
    )
    (net (code "148") (name "unconnected-(U101A-P0[28]{slash}SCL0-Pad48)") (class "Default")
      (node (ref "U101") (pin "48") (pinfunction "P0[28]/SCL0_48") (pintype "bidirectional"))
    )
    (net (code "149") (name "unconnected-(U101A-P0[29]{slash}USB_D+1-Pad61)") (class "Default")
      (node (ref "U101") (pin "61") (pinfunction "P0[29]/USB_D+1_61") (pintype "bidirectional+no_connect"))
    )
    (net (code "150") (name "unconnected-(U101A-P0[30]{slash}USB_D-1-Pad62)") (class "Default")
      (node (ref "U101") (pin "62") (pinfunction "P0[30]/USB_D-1_62") (pintype "bidirectional+no_connect"))
    )
    (net (code "151") (name "unconnected-(U101A-P0[31]{slash}USB_D+2-Pad51)") (class "Default")
      (node (ref "U101") (pin "51") (pinfunction "P0[31]/USB_D+2_51") (pintype "bidirectional+no_connect"))
    )
    (net (code "152") (name "unconnected-(U101B-P1[0]{slash}ENET_TXD0-Pad196)") (class "Default")
      (node (ref "U101") (pin "196") (pinfunction "P1[0]/ENET_TXD0_196") (pintype "bidirectional+no_connect"))
    )
    (net (code "153") (name "unconnected-(U101B-P1[1]{slash}ENET_TXD1-Pad194)") (class "Default")
      (node (ref "U101") (pin "194") (pinfunction "P1[1]/ENET_TXD1_194") (pintype "bidirectional+no_connect"))
    )
    (net (code "154") (name "unconnected-(U101B-P1[2]{slash}ENET_TXD2{slash}MCICLK{slash}PWM0[1]-Pad185)") (class "Default")
      (node (ref "U101") (pin "185") (pinfunction "P1[2]/ENET_TXD2/MCICLK/PWM0[1]_185") (pintype "bidirectional+no_connect"))
    )
    (net (code "155") (name "unconnected-(U101B-P1[3]{slash}ENET_TXD3{slash}MCICMD{slash}PWM0[2]-Pad177)") (class "Default")
      (node (ref "U101") (pin "177") (pinfunction "P1[3]/ENET_TXD3/MCICMD/PWM0[2]_177") (pintype "bidirectional+no_connect"))
    )
    (net (code "156") (name "unconnected-(U101B-P1[4]{slash}ENET_TX_EN-Pad192)") (class "Default")
      (node (ref "U101") (pin "192") (pinfunction "P1[4]/ENET_TX_EN_192") (pintype "bidirectional+no_connect"))
    )
    (net (code "157") (name "unconnected-(U101B-P1[5]{slash}ENET_TX_ER{slash}MCIPWR{slash}PWM0[3]-Pad156)") (class "Default")
      (node (ref "U101") (pin "156") (pinfunction "P1[5]/ENET_TX_ER/MCIPWR/PWM0[3]_156") (pintype "bidirectional+no_connect"))
    )
    (net (code "158") (name "unconnected-(U101B-P1[6]{slash}ENET_TX_CLK{slash}MCIDAT0{slash}PWM0[4]-Pad171)") (class "Default")
      (node (ref "U101") (pin "171") (pinfunction "P1[6]/ENET_TX_CLK/MCIDAT0/PWM0[4]_171") (pintype "bidirectional+no_connect"))
    )
    (net (code "159") (name "unconnected-(U101B-P1[7]{slash}ENET_COL{slash}MCIDAT1{slash}PWM0[5]-Pad153)") (class "Default")
      (node (ref "U101") (pin "153") (pinfunction "P1[7]/ENET_COL/MCIDAT1/PWM0[5]_153") (pintype "bidirectional+no_connect"))
    )
    (net (code "160") (name "unconnected-(U101B-P1[8]{slash}ENET_CRS_DV{slash}ENET_CRS-Pad190)") (class "Default")
      (node (ref "U101") (pin "190") (pinfunction "P1[8]/ENET_CRS_DV/ENET_CRS_190") (pintype "bidirectional+no_connect"))
    )
    (net (code "161") (name "unconnected-(U101B-P1[9]{slash}ENET_RXD0-Pad188)") (class "Default")
      (node (ref "U101") (pin "188") (pinfunction "P1[9]/ENET_RXD0_188") (pintype "bidirectional+no_connect"))
    )
    (net (code "162") (name "unconnected-(U101B-P1[10]{slash}ENET_RXD1-Pad186)") (class "Default")
      (node (ref "U101") (pin "186") (pinfunction "P1[10]/ENET_RXD1_186") (pintype "bidirectional+no_connect"))
    )
    (net (code "163") (name "unconnected-(U101B-P1[11]{slash}ENET_RXD2{slash}MCIDAT2{slash}PWM0[6]-Pad163)") (class "Default")
      (node (ref "U101") (pin "163") (pinfunction "P1[11]/ENET_RXD2/MCIDAT2/PWM0[6]_163") (pintype "bidirectional+no_connect"))
    )
    (net (code "164") (name "unconnected-(U101B-P1[12]{slash}ENET_RXD3{slash}MCIDAT3{slash}PCAP0[0]-Pad157)") (class "Default")
      (node (ref "U101") (pin "157") (pinfunction "P1[12]/ENET_RXD3/MCIDAT3/PCAP0[0]_157") (pintype "bidirectional+no_connect"))
    )
    (net (code "165") (name "unconnected-(U101B-P1[13]{slash}ENET_RX_DV-Pad147)") (class "Default")
      (node (ref "U101") (pin "147") (pinfunction "P1[13]/ENET_RX_DV_147") (pintype "bidirectional+no_connect"))
    )
    (net (code "166") (name "unconnected-(U101B-P1[14]{slash}ENET_RX_ER-Pad184)") (class "Default")
      (node (ref "U101") (pin "184") (pinfunction "P1[14]/ENET_RX_ER_184") (pintype "bidirectional+no_connect"))
    )
    (net (code "167") (name "unconnected-(U101B-P1[15]{slash}ENET_REF_CLK{slash}ENET_RX_CLK-Pad182)") (class "Default")
      (node (ref "U101") (pin "182") (pinfunction "P1[15]/ENET_REF_CLK/ENET_RX_CLK_182") (pintype "bidirectional+no_connect"))
    )
    (net (code "168") (name "unconnected-(U101B-P1[16]{slash}ENET_MDC-Pad180)") (class "Default")
      (node (ref "U101") (pin "180") (pinfunction "P1[16]/ENET_MDC_180") (pintype "bidirectional+no_connect"))
    )
    (net (code "169") (name "unconnected-(U101B-P1[17]{slash}ENET_MDIO-Pad178)") (class "Default")
      (node (ref "U101") (pin "178") (pinfunction "P1[17]/ENET_MDIO_178") (pintype "bidirectional+no_connect"))
    )
    (net (code "170") (name "unconnected-(U101B-P1[18]{slash}USB_UP_LED1{slash}PWM1[1]{slash}CAP1[0]-Pad66)") (class "Default")
      (node (ref "U101") (pin "66") (pinfunction "P1[18]/USB_UP_LED1/PWM1[1]/CAP1[0]_66") (pintype "bidirectional+no_connect"))
    )
    (net (code "171") (name "unconnected-(U101B-P1[27]{slash}~{USB_INT}1{slash}~{USB_OVRCR}1{slash}CAP0[1]-Pad88)") (class "Default")
      (node (ref "U101") (pin "88") (pinfunction "P1[27]/~{USB_INT}1/~{USB_OVRCR}1/CAP0[1]_88") (pintype "bidirectional+no_connect"))
    )
    (net (code "172") (name "unconnected-(U101B-P1[28]{slash}USB_SCL1{slash}PCAP1[0]{slash}MAT0[0]-Pad90)") (class "Default")
      (node (ref "U101") (pin "90") (pinfunction "P1[28]/USB_SCL1/PCAP1[0]/MAT0[0]_90") (pintype "bidirectional+no_connect"))
    )
    (net (code "173") (name "unconnected-(U101B-P1[29]{slash}USB_SDA1{slash}PCAP1[1]{slash}MAT0[1]-Pad92)") (class "Default")
      (node (ref "U101") (pin "92") (pinfunction "P1[29]/USB_SDA1/PCAP1[1]/MAT0[1]_92") (pintype "bidirectional+no_connect"))
    )
    (net (code "174") (name "unconnected-(U101B-P1[30]{slash}USB_PWRD2{slash}VBUS{slash}AD0[4]-Pad42)") (class "Default")
      (node (ref "U101") (pin "42") (pinfunction "P1[30]/USB_PWRD2/VBUS/AD0[4]_42") (pintype "bidirectional+no_connect"))
    )
    (net (code "175") (name "unconnected-(U101B-P1[31]{slash}~{USB_OVRCR}2{slash}SCK1{slash}AD0[5]-Pad40)") (class "Default")
      (node (ref "U101") (pin "40") (pinfunction "P1[31]/~{USB_OVRCR}2/SCK1/AD0[5]_40") (pintype "bidirectional+no_connect"))
    )
    (net (code "176") (name "unconnected-(U101C-P2[0]{slash}PWM1[1]{slash}TXD1{slash}TRACECLK-Pad154)") (class "Default")
      (node (ref "U101") (pin "154") (pinfunction "P2[0]/PWM1[1]/TXD1/TRACECLK_154") (pintype "bidirectional"))
    )
    (net (code "177") (name "unconnected-(U101C-P2[5]{slash}PWM1[6]{slash}DTR1{slash}TRACEPKT0-Pad140)") (class "Default")
      (node (ref "U101") (pin "140") (pinfunction "P2[5]/PWM1[6]/DTR1/TRACEPKT0_140") (pintype "bidirectional"))
    )
    (net (code "178") (name "unconnected-(U101C-P2[14]{slash}~{CS}2{slash}CAP2[0]{slash}SDA1-Pad91)") (class "Default")
      (node (ref "U101") (pin "91") (pinfunction "P2[14]/~{CS}2/CAP2[0]/SDA1_91") (pintype "bidirectional+no_connect"))
    )
    (net (code "179") (name "unconnected-(U101C-P2[16]{slash}~{CAS}-Pad87)") (class "Default")
      (node (ref "U101") (pin "87") (pinfunction "P2[16]/~{CAS}_87") (pintype "bidirectional+no_connect"))
    )
    (net (code "180") (name "unconnected-(U101C-P2[22]{slash}~{DYCS}2{slash}CAP3[0]{slash}SCK0-Pad85)") (class "Default")
      (node (ref "U101") (pin "85") (pinfunction "P2[22]/~{DYCS}2/CAP3[0]/SCK0_85") (pintype "bidirectional+no_connect"))
    )
    (net (code "181") (name "unconnected-(U101C-P2[24]{slash}CKEOUT0-Pad53)") (class "Default")
      (node (ref "U101") (pin "53") (pinfunction "P2[24]/CKEOUT0_53") (pintype "bidirectional+no_connect"))
    )
    (net (code "182") (name "unconnected-(U101C-P2[27]{slash}CKEOUT3{slash}MAT3[1]{slash}MOSI0-Pad47)") (class "Default")
      (node (ref "U101") (pin "47") (pinfunction "P2[27]/CKEOUT3/MAT3[1]/MOSI0_47") (pintype "bidirectional+no_connect"))
    )
    (net (code "183") (name "unconnected-(U101C-P2[28]{slash}DQMOUT0-Pad49)") (class "Default")
      (node (ref "U101") (pin "49") (pinfunction "P2[28]/DQMOUT0_49") (pintype "bidirectional+no_connect"))
    )
    (net (code "184") (name "unconnected-(U101C-P2[29]{slash}DQMOUT1-Pad43)") (class "Default")
      (node (ref "U101") (pin "43") (pinfunction "P2[29]/DQMOUT1_43") (pintype "bidirectional+no_connect"))
    )
    (net (code "185") (name "unconnected-(U101C-P2[30]{slash}DQMOUT2{slash}MAT3[2]{slash}SDA2-Pad31)") (class "Default")
      (node (ref "U101") (pin "31") (pinfunction "P2[30]/DQMOUT2/MAT3[2]/SDA2_31") (pintype "bidirectional+no_connect"))
    )
    (net (code "186") (name "unconnected-(U101C-P2[31]{slash}DQMOUT3{slash}MAT3[3]{slash}SCL2-Pad39)") (class "Default")
      (node (ref "U101") (pin "39") (pinfunction "P2[31]/DQMOUT3/MAT3[3]/SCL2_39") (pintype "bidirectional+no_connect"))
    )
    (net (code "187") (name "unconnected-(U101D-P3[16]{slash}D16{slash}PWM0[1]{slash}TXD1-Pad137)") (class "Default")
      (node (ref "U101") (pin "137") (pinfunction "P3[16]/D16/PWM0[1]/TXD1_137") (pintype "bidirectional+no_connect"))
    )
    (net (code "188") (name "unconnected-(U101D-P3[17]{slash}D17{slash}PWM0[2]{slash}RXD1-Pad143)") (class "Default")
      (node (ref "U101") (pin "143") (pinfunction "P3[17]/D17/PWM0[2]/RXD1_143") (pintype "bidirectional+no_connect"))
    )
    (net (code "189") (name "unconnected-(U101D-P3[18]{slash}D18{slash}PWM0[3]{slash}CTS1-Pad151)") (class "Default")
      (node (ref "U101") (pin "151") (pinfunction "P3[18]/D18/PWM0[3]/CTS1_151") (pintype "bidirectional+no_connect"))
    )
    (net (code "190") (name "unconnected-(U101D-P3[19]{slash}D19{slash}PWM0[4]{slash}DCD1-Pad161)") (class "Default")
      (node (ref "U101") (pin "161") (pinfunction "P3[19]/D19/PWM0[4]/DCD1_161") (pintype "bidirectional+no_connect"))
    )
    (net (code "191") (name "unconnected-(U101D-P3[20]{slash}D20{slash}PWM0[5]{slash}DSR1-Pad167)") (class "Default")
      (node (ref "U101") (pin "167") (pinfunction "P3[20]/D20/PWM0[5]/DSR1_167") (pintype "bidirectional+no_connect"))
    )
    (net (code "192") (name "unconnected-(U101D-P3[21]{slash}D21{slash}PWM0[6]{slash}DTR1-Pad175)") (class "Default")
      (node (ref "U101") (pin "175") (pinfunction "P3[21]/D21/PWM0[6]/DTR1_175") (pintype "bidirectional+no_connect"))
    )
    (net (code "193") (name "unconnected-(U101D-P3[22]{slash}D22{slash}PCAP0[0]{slash}RI1-Pad195)") (class "Default")
      (node (ref "U101") (pin "195") (pinfunction "P3[22]/D22/PCAP0[0]/RI1_195") (pintype "bidirectional+no_connect"))
    )
    (net (code "194") (name "unconnected-(U101D-P3[27]{slash}D27{slash}CAP1[0]{slash}PWM1[4]-Pad203)") (class "Default")
      (node (ref "U101") (pin "203") (pinfunction "P3[27]/D27/CAP1[0]/PWM1[4]_203") (pintype "bidirectional+no_connect"))
    )
    (net (code "195") (name "unconnected-(U101D-P3[28]{slash}D28{slash}CAP1[1]{slash}PWM1[5]-Pad5)") (class "Default")
      (node (ref "U101") (pin "5") (pinfunction "P3[28]/D28/CAP1[1]/PWM1[5]_5") (pintype "bidirectional+no_connect"))
    )
    (net (code "196") (name "unconnected-(U101D-P3[29]{slash}D29{slash}MAT1[0]{slash}PWM1[6]-Pad11)") (class "Default")
      (node (ref "U101") (pin "11") (pinfunction "P3[29]/D29/MAT1[0]/PWM1[6]_11") (pintype "bidirectional+no_connect"))
    )
    (net (code "197") (name "unconnected-(U101D-P3[30]{slash}D30{slash}MAT1[1]{slash}RTS1-Pad19)") (class "Default")
      (node (ref "U101") (pin "19") (pinfunction "P3[30]/D30/MAT1[1]/RTS1_19") (pintype "bidirectional+no_connect"))
    )
    (net (code "198") (name "unconnected-(U101D-P3[31]{slash}D31{slash}MAT1[2]-Pad25)") (class "Default")
      (node (ref "U101") (pin "25") (pinfunction "P3[31]/D31/MAT1[2]_25") (pintype "bidirectional+no_connect"))
    )
    (net (code "199") (name "unconnected-(U101E-P4[0]{slash}A0-Pad75)") (class "Default")
      (node (ref "U101") (pin "75") (pinfunction "P4[0]/A0_75") (pintype "bidirectional+no_connect"))
    )
    (net (code "200") (name "unconnected-(U101E-P4[28]{slash}BLS2{slash}MAT2[0]{slash}TXD3-Pad170)") (class "Default")
      (node (ref "U101") (pin "170") (pinfunction "P4[28]/BLS2/MAT2[0]/TXD3_170") (pintype "bidirectional+no_connect"))
    )
    (net (code "201") (name "unconnected-(U101E-P4[29]{slash}BLS3{slash}MAT2[1]{slash}RXD3-Pad176)") (class "Default")
      (node (ref "U101") (pin "176") (pinfunction "P4[29]/BLS3/MAT2[1]/RXD3_176") (pintype "bidirectional+no_connect"))
    )
    (net (code "202") (name "unconnected-(U101F-ALARM-Pad37)") (class "Default")
      (node (ref "U101") (pin "37") (pinfunction "ALARM_37") (pintype "output+no_connect"))
    )
    (net (code "203") (name "unconnected-(U101F-USB_D-2-Pad52)") (class "Default")
      (node (ref "U101") (pin "52") (pinfunction "USB_D-2_52") (pintype "bidirectional+no_connect"))
    )
    (net (code "204") (name "unconnected-(U101I-NC-Pad30)") (class "Default")
      (node (ref "U101") (pin "30") (pinfunction "NC_30") (pintype "passive+no_connect"))
    )
    (net (code "205") (name "unconnected-(U101I-NC-Pad117)") (class "Default")
      (node (ref "U101") (pin "117") (pinfunction "NC_117") (pintype "passive+no_connect"))
    )
    (net (code "206") (name "unconnected-(U101I-NC-Pad141)") (class "Default")
      (node (ref "U101") (pin "141") (pinfunction "NC_141") (pintype "passive+no_connect"))
    )
    (net (code "207") (name "unconnected-(U102-DNU-Pad13)") (class "Default")
      (node (ref "U102") (pin "13") (pinfunction "DNU_13") (pintype "passive+no_connect"))
    )
    (net (code "208") (name "unconnected-(U102-NC-Pad10)") (class "Default")
      (node (ref "U102") (pin "10") (pinfunction "NC_10") (pintype "passive+no_connect"))
    )
  )
)
